# MMA8452Q-breakout-v1_1.net
KiCad netlist of a schematic drawn in EAGLE
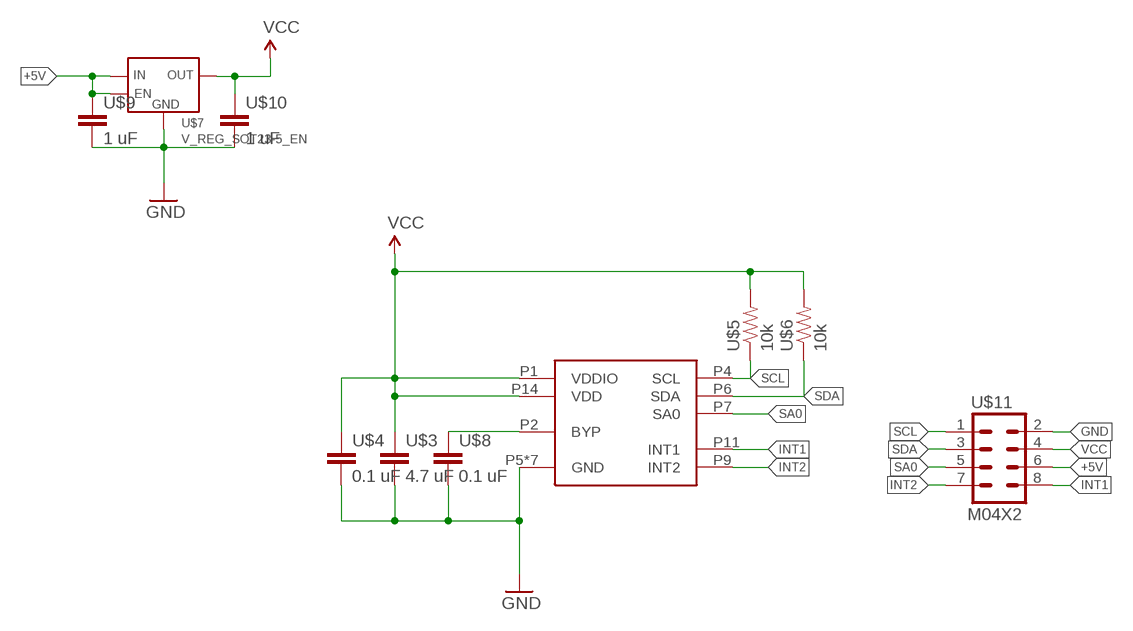
[diagram p0: schematic, sheet 1]

(export (version "E")
  (design (tool "Eeschema 10.0.6"))
  (components
    (comp (ref "U$2")
      (value "MMA_8452")
      (footprint "eagle-import:QFN-16-MMA")
      (libsource (lib "eagle-import") (part "MMA_8452"))
    )
    (comp (ref "U$3")
      (value "4.7 uF")
      (footprint "eagle-import:CAP-0603")
      (libsource (lib "eagle-import") (part "CAPCAP-0603"))
    )
    (comp (ref "U$4")
      (value "0.1 uF")
      (footprint "eagle-import:CAP-0603")
      (libsource (lib "eagle-import") (part "CAPCAP-0603"))
    )
    (comp (ref "U$5")
      (value "10k")
      (footprint "eagle-import:RES-0603")
      (libsource (lib "eagle-import") (part "RESISTOR0603"))
    )
    (comp (ref "U$6")
      (value "10k")
      (footprint "eagle-import:RES-0603")
      (libsource (lib "eagle-import") (part "RESISTOR0603"))
    )
    (comp (ref "U$7")
      (value "V_REG_SOT23-5_EN")
      (footprint "eagle-import:SOT23-5")
      (libsource (lib "eagle-import") (part "V_REG_SOT23-5_EN"))
    )
    (comp (ref "U$8")
      (value "0.1 uF")
      (footprint "eagle-import:CAP-0603")
      (libsource (lib "eagle-import") (part "CAPCAP-0603"))
    )
    (comp (ref "U$9")
      (value "1 uF")
      (footprint "eagle-import:CAP-0603")
      (libsource (lib "eagle-import") (part "CAPCAP-0603"))
    )
    (comp (ref "U$10")
      (value "1 uF")
      (footprint "eagle-import:CAP-0603")
      (libsource (lib "eagle-import") (part "CAPCAP-0603"))
    )
    (comp (ref "U$11")
      (value "M04X2")
      (footprint "eagle-import:2X4")
      (libsource (lib "eagle-import") (part "M04X2"))
    )
  )
  (nets
    (net (code "1") (name "+5V") (class "Default")
      (node (ref "U$11") (pin "6") (pinfunction "6_6") (pintype "passive"))
      (node (ref "U$7") (pin "1") (pinfunction "IN_1") (pintype "input"))
      (node (ref "U$7") (pin "3") (pinfunction "EN_3") (pintype "input"))
      (node (ref "U$9") (pin "1") (pinfunction "1_1") (pintype "passive"))
    )
    (net (code "2") (name "GND") (class "Default")
      (node (ref "U$10") (pin "2") (pinfunction "2_2") (pintype "passive"))
      (node (ref "U$11") (pin "2") (pinfunction "2_2") (pintype "passive"))
      (node (ref "U$2") (pin "P10") (pinfunction "GND_P10") (pintype "power_in"))
      (node (ref "U$2") (pin "P12") (pinfunction "GND_P12") (pintype "power_in"))
      (node (ref "U$2") (pin "P13") (pinfunction "GND_P13") (pintype "power_in"))
      (node (ref "U$2") (pin "P15") (pinfunction "GND_P15") (pintype "power_in"))
      (node (ref "U$2") (pin "P16") (pinfunction "GND_P16") (pintype "power_in"))
      (node (ref "U$2") (pin "P5") (pinfunction "GND_P5") (pintype "power_in"))
      (node (ref "U$2") (pin "P8") (pinfunction "GND_P8") (pintype "power_in"))
      (node (ref "U$3") (pin "2") (pinfunction "2_2") (pintype "passive"))
      (node (ref "U$4") (pin "2") (pinfunction "2_2") (pintype "passive"))
      (node (ref "U$7") (pin "2") (pinfunction "GND_2") (pintype "input"))
      (node (ref "U$8") (pin "2") (pinfunction "2_2") (pintype "passive"))
      (node (ref "U$9") (pin "2") (pinfunction "2_2") (pintype "passive"))
    )
    (net (code "3") (name "INT1") (class "Default")
      (node (ref "U$11") (pin "8") (pinfunction "8_8") (pintype "passive"))
      (node (ref "U$2") (pin "P11") (pinfunction "INT1_P11") (pintype "bidirectional"))
    )
    (net (code "4") (name "INT2") (class "Default")
      (node (ref "U$11") (pin "7") (pinfunction "7_7") (pintype "passive"))
      (node (ref "U$2") (pin "P9") (pinfunction "INT2_P9") (pintype "bidirectional"))
    )
    (net (code "5") (name "Net-(U$2-BYP)") (class "Default")
      (node (ref "U$2") (pin "P2") (pinfunction "BYP_P2") (pintype "bidirectional"))
      (node (ref "U$8") (pin "1") (pinfunction "1_1") (pintype "passive"))
    )
    (net (code "6") (name "SA0") (class "Default")
      (node (ref "U$11") (pin "5") (pinfunction "5_5") (pintype "passive"))
      (node (ref "U$2") (pin "P7") (pinfunction "SA0_P7") (pintype "bidirectional"))
    )
    (net (code "7") (name "SCL") (class "Default")
      (node (ref "U$11") (pin "1") (pinfunction "1_1") (pintype "passive"))
      (node (ref "U$2") (pin "P4") (pinfunction "SCL_P4") (pintype "bidirectional"))
      (node (ref "U$5") (pin "1") (pinfunction "1_1") (pintype "passive"))
    )
    (net (code "8") (name "SDA") (class "Default")
      (node (ref "U$11") (pin "3") (pinfunction "3_3") (pintype "passive"))
      (node (ref "U$2") (pin "P6") (pinfunction "SDA_P6") (pintype "bidirectional"))
      (node (ref "U$6") (pin "1") (pinfunction "1_1") (pintype "passive"))
    )
    (net (code "9") (name "VCC") (class "Default")
      (node (ref "U$10") (pin "1") (pinfunction "1_1") (pintype "passive"))
      (node (ref "U$11") (pin "4") (pinfunction "4_4") (pintype "passive"))
      (node (ref "U$2") (pin "P1") (pinfunction "VDDIO_P1") (pintype "power_in"))
      (node (ref "U$2") (pin "P14") (pinfunction "VDD_P14") (pintype "power_in"))
      (node (ref "U$3") (pin "1") (pinfunction "1_1") (pintype "passive"))
      (node (ref "U$4") (pin "1") (pinfunction "1_1") (pintype "passive"))
      (node (ref "U$5") (pin "2") (pinfunction "2_2") (pintype "passive"))
      (node (ref "U$6") (pin "2") (pinfunction "2_2") (pintype "passive"))
      (node (ref "U$7") (pin "5") (pinfunction "OUT_5") (pintype "passive"))
    )
  )
)
